# PSX-PS2.net
KiCad netlist of a schematic drawn in EAGLE
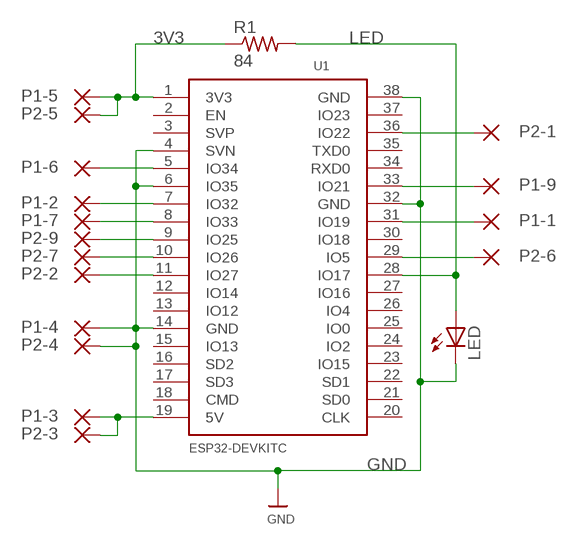
[diagram p0: schematic, sheet 1]

(export (version "E")
  (design (tool "Eeschema 10.0.6"))
  (components
    (comp (ref "LED")
      (value "LEDCHIPLED_1206")
      (footprint "eagle-import:CHIPLED_1206")
      (libsource (lib "eagle-import") (part "LEDCHIPLED_1206"))
    )
    (comp (ref "P1-1")
      (value "SMD5")
      (footprint "eagle-import:SMD2,54-5,08")
      (libsource (lib "eagle-import") (part "SMD5"))
    )
    (comp (ref "P1-2")
      (value "SMD5")
      (footprint "eagle-import:SMD2,54-5,08")
      (libsource (lib "eagle-import") (part "SMD5"))
    )
    (comp (ref "P1-3")
      (value "SMD5")
      (footprint "eagle-import:SMD2,54-5,08")
      (libsource (lib "eagle-import") (part "SMD5"))
    )
    (comp (ref "P1-4")
      (value "SMD5")
      (footprint "eagle-import:SMD2,54-5,08")
      (libsource (lib "eagle-import") (part "SMD5"))
    )
    (comp (ref "P1-5")
      (value "SMD5")
      (footprint "eagle-import:SMD2,54-5,08")
      (libsource (lib "eagle-import") (part "SMD5"))
    )
    (comp (ref "P1-6")
      (value "SMD5")
      (footprint "eagle-import:SMD2,54-5,08")
      (libsource (lib "eagle-import") (part "SMD5"))
    )
    (comp (ref "P1-7")
      (value "SMD5")
      (footprint "eagle-import:SMD2,54-5,08")
      (libsource (lib "eagle-import") (part "SMD5"))
    )
    (comp (ref "P1-9")
      (value "SMD5")
      (footprint "eagle-import:SMD2,54-5,08")
      (libsource (lib "eagle-import") (part "SMD5"))
    )
    (comp (ref "P2-1")
      (value "SMD5")
      (footprint "eagle-import:SMD2,54-5,08")
      (libsource (lib "eagle-import") (part "SMD5"))
    )
    (comp (ref "P2-2")
      (value "SMD5")
      (footprint "eagle-import:SMD2,54-5,08")
      (libsource (lib "eagle-import") (part "SMD5"))
    )
    (comp (ref "P2-3")
      (value "SMD5")
      (footprint "eagle-import:SMD2,54-5,08")
      (libsource (lib "eagle-import") (part "SMD5"))
    )
    (comp (ref "P2-4")
      (value "SMD5")
      (footprint "eagle-import:SMD2,54-5,08")
      (libsource (lib "eagle-import") (part "SMD5"))
    )
    (comp (ref "P2-5")
      (value "SMD5")
      (footprint "eagle-import:SMD2,54-5,08")
      (libsource (lib "eagle-import") (part "SMD5"))
    )
    (comp (ref "P2-6")
      (value "SMD5")
      (footprint "eagle-import:SMD2,54-5,08")
      (libsource (lib "eagle-import") (part "SMD5"))
    )
    (comp (ref "P2-7")
      (value "SMD5")
      (footprint "eagle-import:SMD2,54-5,08")
      (libsource (lib "eagle-import") (part "SMD5"))
    )
    (comp (ref "P2-9")
      (value "SMD5")
      (footprint "eagle-import:SMD2,54-5,08")
      (libsource (lib "eagle-import") (part "SMD5"))
    )
    (comp (ref "R1")
      (value "84")
      (footprint "eagle-import:R1206")
      (libsource (lib "eagle-import") (part "R-US_R1206"))
    )
    (comp (ref "U1")
      (value "ESP32DEVKITC")
      (footprint "eagle-import:ESP32-DEVKITC")
      (libsource (lib "eagle-import") (part "ESP32DEVKITC"))
    )
  )
  (nets
    (net (code "1") (name "/3V3") (class "Default")
      (node (ref "P1-5") (pin "1") (pinfunction "P_1") (pintype "passive"))
      (node (ref "P2-5") (pin "1") (pinfunction "P_1") (pintype "passive"))
      (node (ref "R1") (pin "1") (pinfunction "1_1") (pintype "passive"))
      (node (ref "U1") (pin "1") (pinfunction "3V3_1") (pintype "bidirectional"))
    )
    (net (code "2") (name "/LED") (class "Default")
      (node (ref "LED") (pin "A") (pinfunction "A_A") (pintype "passive"))
      (node (ref "R1") (pin "2") (pinfunction "2_2") (pintype "passive"))
      (node (ref "U1") (pin "28") (pinfunction "IO17_28") (pintype "bidirectional"))
    )
    (net (code "3") (name "GND") (class "Default")
      (node (ref "LED") (pin "C") (pinfunction "C_C") (pintype "passive"))
      (node (ref "P1-4") (pin "1") (pinfunction "P_1") (pintype "passive"))
      (node (ref "P2-4") (pin "1") (pinfunction "P_1") (pintype "passive"))
      (node (ref "U1") (pin "14") (pinfunction "GND_14") (pintype "bidirectional"))
      (node (ref "U1") (pin "32") (pinfunction "GND_32") (pintype "bidirectional"))
      (node (ref "U1") (pin "38") (pinfunction "GND_38") (pintype "bidirectional"))
      (node (ref "U1") (pin "4") (pinfunction "SVN_4") (pintype "bidirectional"))
      (node (ref "U1") (pin "6") (pinfunction "IO35_6") (pintype "bidirectional"))
    )
    (net (code "4") (name "Net-(P1-1-P)") (class "Default")
      (node (ref "P1-1") (pin "1") (pinfunction "P_1") (pintype "passive"))
      (node (ref "U1") (pin "31") (pinfunction "IO19_31") (pintype "bidirectional"))
    )
    (net (code "5") (name "Net-(P1-2-P)") (class "Default")
      (node (ref "P1-2") (pin "1") (pinfunction "P_1") (pintype "passive"))
      (node (ref "U1") (pin "7") (pinfunction "IO32_7") (pintype "bidirectional"))
    )
    (net (code "6") (name "Net-(P1-3-P)") (class "Default")
      (node (ref "P1-3") (pin "1") (pinfunction "P_1") (pintype "passive"))
      (node (ref "P2-3") (pin "1") (pinfunction "P_1") (pintype "passive"))
      (node (ref "U1") (pin "19") (pinfunction "5V_19") (pintype "bidirectional"))
    )
    (net (code "7") (name "Net-(P1-6-P)") (class "Default")
      (node (ref "P1-6") (pin "1") (pinfunction "P_1") (pintype "passive"))
      (node (ref "U1") (pin "5") (pinfunction "IO34_5") (pintype "bidirectional"))
    )
    (net (code "8") (name "Net-(P1-7-P)") (class "Default")
      (node (ref "P1-7") (pin "1") (pinfunction "P_1") (pintype "passive"))
      (node (ref "U1") (pin "8") (pinfunction "IO33_8") (pintype "bidirectional"))
    )
    (net (code "9") (name "Net-(P1-9-P)") (class "Default")
      (node (ref "P1-9") (pin "1") (pinfunction "P_1") (pintype "passive"))
      (node (ref "U1") (pin "33") (pinfunction "IO21_33") (pintype "bidirectional"))
    )
    (net (code "10") (name "Net-(P2-1-P)") (class "Default")
      (node (ref "P2-1") (pin "1") (pinfunction "P_1") (pintype "passive"))
      (node (ref "U1") (pin "36") (pinfunction "IO22_36") (pintype "bidirectional"))
    )
    (net (code "11") (name "Net-(P2-2-P)") (class "Default")
      (node (ref "P2-2") (pin "1") (pinfunction "P_1") (pintype "passive"))
      (node (ref "U1") (pin "11") (pinfunction "IO27_11") (pintype "bidirectional"))
    )
    (net (code "12") (name "Net-(P2-6-P)") (class "Default")
      (node (ref "P2-6") (pin "1") (pinfunction "P_1") (pintype "passive"))
      (node (ref "U1") (pin "29") (pinfunction "IO5_29") (pintype "bidirectional"))
    )
    (net (code "13") (name "Net-(P2-7-P)") (class "Default")
      (node (ref "P2-7") (pin "1") (pinfunction "P_1") (pintype "passive"))
      (node (ref "U1") (pin "10") (pinfunction "IO26_10") (pintype "bidirectional"))
    )
    (net (code "14") (name "Net-(P2-9-P)") (class "Default")
      (node (ref "P2-9") (pin "1") (pinfunction "P_1") (pintype "passive"))
      (node (ref "U1") (pin "9") (pinfunction "IO25_9") (pintype "bidirectional"))
    )
    (net (code "15") (name "unconnected-(U1-CLK-Pad20)") (class "Default")
      (node (ref "U1") (pin "20") (pinfunction "CLK_20") (pintype "bidirectional"))
    )
    (net (code "16") (name "unconnected-(U1-CMD-Pad18)") (class "Default")
      (node (ref "U1") (pin "18") (pinfunction "CMD_18") (pintype "bidirectional"))
    )
    (net (code "17") (name "unconnected-(U1-EN-Pad2)") (class "Default")
      (node (ref "U1") (pin "2") (pinfunction "EN_2") (pintype "bidirectional"))
    )
    (net (code "18") (name "unconnected-(U1-IO0-Pad25)") (class "Default")
      (node (ref "U1") (pin "25") (pinfunction "IO0_25") (pintype "bidirectional"))
    )
    (net (code "19") (name "unconnected-(U1-IO2-Pad24)") (class "Default")
      (node (ref "U1") (pin "24") (pinfunction "IO2_24") (pintype "bidirectional"))
    )
    (net (code "20") (name "unconnected-(U1-IO4-Pad26)") (class "Default")
      (node (ref "U1") (pin "26") (pinfunction "IO4_26") (pintype "bidirectional"))
    )
    (net (code "21") (name "unconnected-(U1-IO12-Pad13)") (class "Default")
      (node (ref "U1") (pin "13") (pinfunction "IO12_13") (pintype "bidirectional"))
    )
    (net (code "22") (name "unconnected-(U1-IO13-Pad15)") (class "Default")
      (node (ref "U1") (pin "15") (pinfunction "IO13_15") (pintype "bidirectional"))
    )
    (net (code "23") (name "unconnected-(U1-IO14-Pad12)") (class "Default")
      (node (ref "U1") (pin "12") (pinfunction "IO14_12") (pintype "bidirectional"))
    )
    (net (code "24") (name "unconnected-(U1-IO15-Pad23)") (class "Default")
      (node (ref "U1") (pin "23") (pinfunction "IO15_23") (pintype "bidirectional"))
    )
    (net (code "25") (name "unconnected-(U1-IO16-Pad27)") (class "Default")
      (node (ref "U1") (pin "27") (pinfunction "IO16_27") (pintype "bidirectional"))
    )
    (net (code "26") (name "unconnected-(U1-IO18-Pad30)") (class "Default")
      (node (ref "U1") (pin "30") (pinfunction "IO18_30") (pintype "bidirectional"))
    )
    (net (code "27") (name "unconnected-(U1-IO23-Pad37)") (class "Default")
      (node (ref "U1") (pin "37") (pinfunction "IO23_37") (pintype "bidirectional"))
    )
    (net (code "28") (name "unconnected-(U1-RXD0-Pad34)") (class "Default")
      (node (ref "U1") (pin "34") (pinfunction "RXD0_34") (pintype "bidirectional"))
    )
    (net (code "29") (name "unconnected-(U1-SD0-Pad21)") (class "Default")
      (node (ref "U1") (pin "21") (pinfunction "SD0_21") (pintype "bidirectional"))
    )
    (net (code "30") (name "unconnected-(U1-SD1-Pad22)") (class "Default")
      (node (ref "U1") (pin "22") (pinfunction "SD1_22") (pintype "bidirectional"))
    )
    (net (code "31") (name "unconnected-(U1-SD2-Pad16)") (class "Default")
      (node (ref "U1") (pin "16") (pinfunction "SD2_16") (pintype "bidirectional"))
    )
    (net (code "32") (name "unconnected-(U1-SD3-Pad17)") (class "Default")
      (node (ref "U1") (pin "17") (pinfunction "SD3_17") (pintype "bidirectional"))
    )
    (net (code "33") (name "unconnected-(U1-SVP-Pad3)") (class "Default")
      (node (ref "U1") (pin "3") (pinfunction "SVP_3") (pintype "bidirectional"))
    )
    (net (code "34") (name "unconnected-(U1-TXD0-Pad35)") (class "Default")
      (node (ref "U1") (pin "35") (pinfunction "TXD0_35") (pintype "bidirectional"))
    )
  )
)
